# 08_-_MAIN_CONNECTOR.net
KiCad netlist of a schematic drawn in Altium Designer
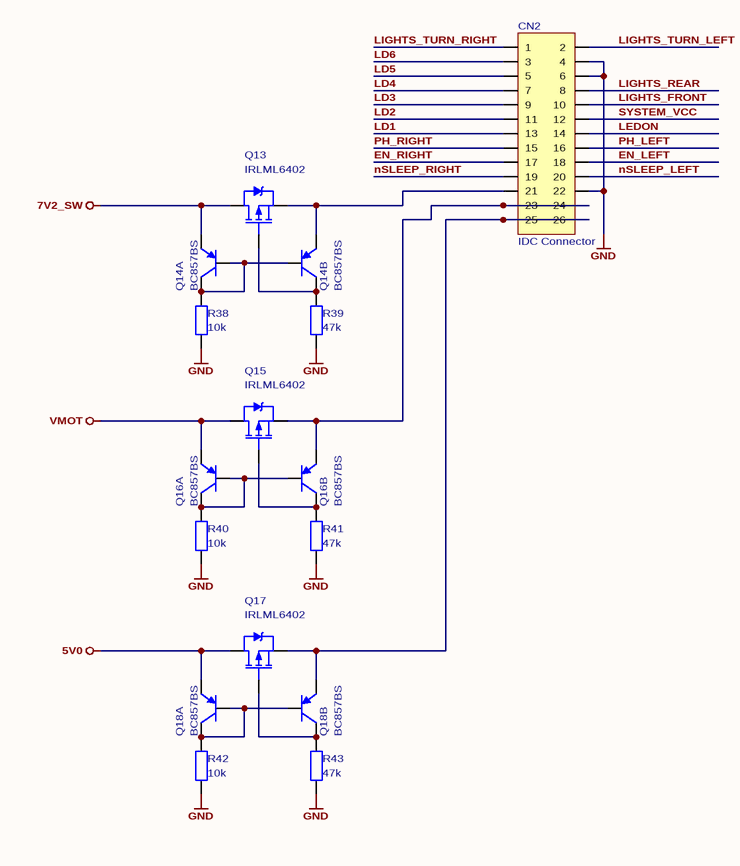
[diagram p0: [08] - MAIN CONNECTOR.SchDoc]

(export (version "E")
  (design (tool "Eeschema 10.0.6"))
  (components
    (comp (ref "CN2")
      (value "IDC Connector")
      (footprint "IDC26_RA_LONG_W_CN")
      (libsource (lib "idc") (part "CN_13x2"))
    )
    (comp (ref "Q13")
      (value "IRLML6402")
      (footprint "SOT-23")
      (description "P-Channel; -20V, -3.7A, 1.3W; HEXFET Power MOS-FET")
      (libsource (lib "transistors_mos") (part "IRLML6402"))
    )
    (comp (ref "Q14")
      (value "BC857BS")
      (footprint "SOT-323-6 (SOT-363, SC88, SC70-6)")
      (description "2xPNP General Purpose Transistor (VCE=-45V, IC=-100mA)")
      (libsource (lib "transistors_bjt") (part "BC857BS"))
    )
    (comp (ref "Q15")
      (value "IRLML6402")
      (footprint "SOT-23")
      (description "P-Channel; -20V, -3.7A, 1.3W; HEXFET Power MOS-FET")
      (libsource (lib "transistors_mos") (part "IRLML6402"))
    )
    (comp (ref "Q16")
      (value "BC857BS")
      (footprint "SOT-323-6 (SOT-363, SC88, SC70-6)")
      (description "2xPNP General Purpose Transistor (VCE=-45V, IC=-100mA)")
      (libsource (lib "transistors_bjt") (part "BC857BS"))
    )
    (comp (ref "Q17")
      (value "IRLML6402")
      (footprint "SOT-23")
      (description "P-Channel; -20V, -3.7A, 1.3W; HEXFET Power MOS-FET")
      (libsource (lib "transistors_mos") (part "IRLML6402"))
    )
    (comp (ref "Q18")
      (value "BC857BS")
      (footprint "SOT-323-6 (SOT-363, SC88, SC70-6)")
      (description "2xPNP General Purpose Transistor (VCE=-45V, IC=-100mA)")
      (libsource (lib "transistors_bjt") (part "BC857BS"))
    )
    (comp (ref "R38")
      (value "10k")
      (footprint "R0805")
      (description "Resistor")
      (libsource (lib "resistors") (part "Res"))
    )
    (comp (ref "R39")
      (value "47k")
      (footprint "R0805")
      (description "Resistor")
      (libsource (lib "resistors") (part "Res"))
    )
    (comp (ref "R40")
      (value "10k")
      (footprint "R0805")
      (description "Resistor")
      (libsource (lib "resistors") (part "Res"))
    )
    (comp (ref "R41")
      (value "47k")
      (footprint "R0805")
      (description "Resistor")
      (libsource (lib "resistors") (part "Res"))
    )
    (comp (ref "R42")
      (value "10k")
      (footprint "R0805")
      (description "Resistor")
      (libsource (lib "resistors") (part "Res"))
    )
    (comp (ref "R43")
      (value "47k")
      (footprint "R0805")
      (description "Resistor")
      (libsource (lib "resistors") (part "Res"))
    )
  )
  (nets
    (net (code "1") (name "/EN_LEFT") (class "Default")
      (node (ref "CN2") (pin "18") (pinfunction "18_18") (pintype "passive"))
    )
    (net (code "2") (name "/EN_RIGHT") (class "Default")
      (node (ref "CN2") (pin "17") (pinfunction "17_17") (pintype "passive"))
    )
    (net (code "3") (name "/LD1") (class "Default")
      (node (ref "CN2") (pin "13") (pinfunction "13_13") (pintype "passive"))
    )
    (net (code "4") (name "/LD2") (class "Default")
      (node (ref "CN2") (pin "11") (pinfunction "11_11") (pintype "passive"))
    )
    (net (code "5") (name "/LD3") (class "Default")
      (node (ref "CN2") (pin "9") (pinfunction "9_9") (pintype "passive"))
    )
    (net (code "6") (name "/LD4") (class "Default")
      (node (ref "CN2") (pin "7") (pinfunction "7_7") (pintype "passive"))
    )
    (net (code "7") (name "/LD5") (class "Default")
      (node (ref "CN2") (pin "5") (pinfunction "5_5") (pintype "passive"))
    )
    (net (code "8") (name "/LD6") (class "Default")
      (node (ref "CN2") (pin "3") (pinfunction "3_3") (pintype "passive"))
    )
    (net (code "9") (name "/LEDON") (class "Default")
      (node (ref "CN2") (pin "14") (pinfunction "14_14") (pintype "passive"))
    )
    (net (code "10") (name "/LIGHTS_FRONT") (class "Default")
      (node (ref "CN2") (pin "10") (pinfunction "10_10") (pintype "passive"))
    )
    (net (code "11") (name "/LIGHTS_REAR") (class "Default")
      (node (ref "CN2") (pin "8") (pinfunction "8_8") (pintype "passive"))
    )
    (net (code "12") (name "/LIGHTS_TURN_LEFT") (class "Default")
      (node (ref "CN2") (pin "2") (pinfunction "2_2") (pintype "passive"))
    )
    (net (code "13") (name "/LIGHTS_TURN_RIGHT") (class "Default")
      (node (ref "CN2") (pin "1") (pinfunction "1_1") (pintype "passive"))
    )
    (net (code "14") (name "/PH_LEFT") (class "Default")
      (node (ref "CN2") (pin "16") (pinfunction "16_16") (pintype "passive"))
    )
    (net (code "15") (name "/PH_RIGHT") (class "Default")
      (node (ref "CN2") (pin "15") (pinfunction "15_15") (pintype "passive"))
    )
    (net (code "16") (name "/SYSTEM_VCC") (class "Default")
      (node (ref "CN2") (pin "12") (pinfunction "12_12") (pintype "passive"))
    )
    (net (code "17") (name "/nSLEEP_LEFT") (class "Default")
      (node (ref "CN2") (pin "20") (pinfunction "20_20") (pintype "passive"))
    )
    (net (code "18") (name "/nSLEEP_RIGHT") (class "Default")
      (node (ref "CN2") (pin "19") (pinfunction "19_19") (pintype "passive"))
    )
    (net (code "19") (name "5V0") (class "Default")
      (node (ref "Q17") (pin "3") (pinfunction "D_3") (pintype "passive"))
      (node (ref "Q18") (pin "1") (pinfunction "EA_1") (pintype "passive"))
    )
    (net (code "20") (name "7V2_SW") (class "Default")
      (node (ref "Q13") (pin "3") (pinfunction "D_3") (pintype "passive"))
      (node (ref "Q14") (pin "1") (pinfunction "EA_1") (pintype "passive"))
    )
    (net (code "21") (name "GND") (class "Default")
      (node (ref "CN2") (pin "22") (pinfunction "22_22") (pintype "passive"))
      (node (ref "CN2") (pin "4") (pinfunction "4_4") (pintype "passive"))
      (node (ref "CN2") (pin "6") (pinfunction "6_6") (pintype "passive"))
      (node (ref "R38") (pin "1") (pinfunction "1_1") (pintype "passive"))
      (node (ref "R39") (pin "1") (pinfunction "1_1") (pintype "passive"))
      (node (ref "R40") (pin "1") (pinfunction "1_1") (pintype "passive"))
      (node (ref "R41") (pin "1") (pinfunction "1_1") (pintype "passive"))
      (node (ref "R42") (pin "1") (pinfunction "1_1") (pintype "passive"))
      (node (ref "R43") (pin "1") (pinfunction "1_1") (pintype "passive"))
    )
    (net (code "22") (name "Net-(Q13-G)") (class "Default")
      (node (ref "Q13") (pin "1") (pinfunction "G_1") (pintype "passive"))
      (node (ref "Q14") (pin "3") (pinfunction "CB_3") (pintype "passive"))
      (node (ref "R39") (pin "2") (pinfunction "2_2") (pintype "passive"))
    )
    (net (code "23") (name "Net-(Q13-S)") (class "Default")
      (node (ref "CN2") (pin "21") (pinfunction "21_21") (pintype "passive"))
      (node (ref "Q13") (pin "2") (pinfunction "S_2") (pintype "passive"))
      (node (ref "Q14") (pin "4") (pinfunction "EB_4") (pintype "passive"))
    )
    (net (code "24") (name "Net-(Q14A-BA)") (class "Default")
      (node (ref "Q14") (pin "2") (pinfunction "BA_2") (pintype "passive"))
      (node (ref "Q14") (pin "5") (pinfunction "BB_5") (pintype "passive"))
      (node (ref "Q14") (pin "6") (pinfunction "CA_6") (pintype "passive"))
      (node (ref "R38") (pin "2") (pinfunction "2_2") (pintype "passive"))
    )
    (net (code "25") (name "Net-(Q15-G)") (class "Default")
      (node (ref "Q15") (pin "1") (pinfunction "G_1") (pintype "passive"))
      (node (ref "Q16") (pin "3") (pinfunction "CB_3") (pintype "passive"))
      (node (ref "R41") (pin "2") (pinfunction "2_2") (pintype "passive"))
    )
    (net (code "26") (name "Net-(Q15-S)") (class "Default")
      (node (ref "CN2") (pin "23") (pinfunction "23_23") (pintype "passive"))
      (node (ref "CN2") (pin "24") (pinfunction "24_24") (pintype "passive"))
      (node (ref "Q15") (pin "2") (pinfunction "S_2") (pintype "passive"))
      (node (ref "Q16") (pin "4") (pinfunction "EB_4") (pintype "passive"))
    )
    (net (code "27") (name "Net-(Q16A-BA)") (class "Default")
      (node (ref "Q16") (pin "2") (pinfunction "BA_2") (pintype "passive"))
      (node (ref "Q16") (pin "5") (pinfunction "BB_5") (pintype "passive"))
      (node (ref "Q16") (pin "6") (pinfunction "CA_6") (pintype "passive"))
      (node (ref "R40") (pin "2") (pinfunction "2_2") (pintype "passive"))
    )
    (net (code "28") (name "Net-(Q17-G)") (class "Default")
      (node (ref "Q17") (pin "1") (pinfunction "G_1") (pintype "passive"))
      (node (ref "Q18") (pin "3") (pinfunction "CB_3") (pintype "passive"))
      (node (ref "R43") (pin "2") (pinfunction "2_2") (pintype "passive"))
    )
    (net (code "29") (name "Net-(Q17-S)") (class "Default")
      (node (ref "CN2") (pin "25") (pinfunction "25_25") (pintype "passive"))
      (node (ref "CN2") (pin "26") (pinfunction "26_26") (pintype "passive"))
      (node (ref "Q17") (pin "2") (pinfunction "S_2") (pintype "passive"))
      (node (ref "Q18") (pin "4") (pinfunction "EB_4") (pintype "passive"))
    )
    (net (code "30") (name "Net-(Q18A-BA)") (class "Default")
      (node (ref "Q18") (pin "2") (pinfunction "BA_2") (pintype "passive"))
      (node (ref "Q18") (pin "5") (pinfunction "BB_5") (pintype "passive"))
      (node (ref "Q18") (pin "6") (pinfunction "CA_6") (pintype "passive"))
      (node (ref "R42") (pin "2") (pinfunction "2_2") (pintype "passive"))
    )
    (net (code "31") (name "VMOT") (class "Default")
      (node (ref "Q15") (pin "3") (pinfunction "D_3") (pintype "passive"))
      (node (ref "Q16") (pin "1") (pinfunction "EA_1") (pintype "passive"))
    )
  )
)
